# ts808_redraw.net
KiCad netlist of a schematic drawn in EAGLE
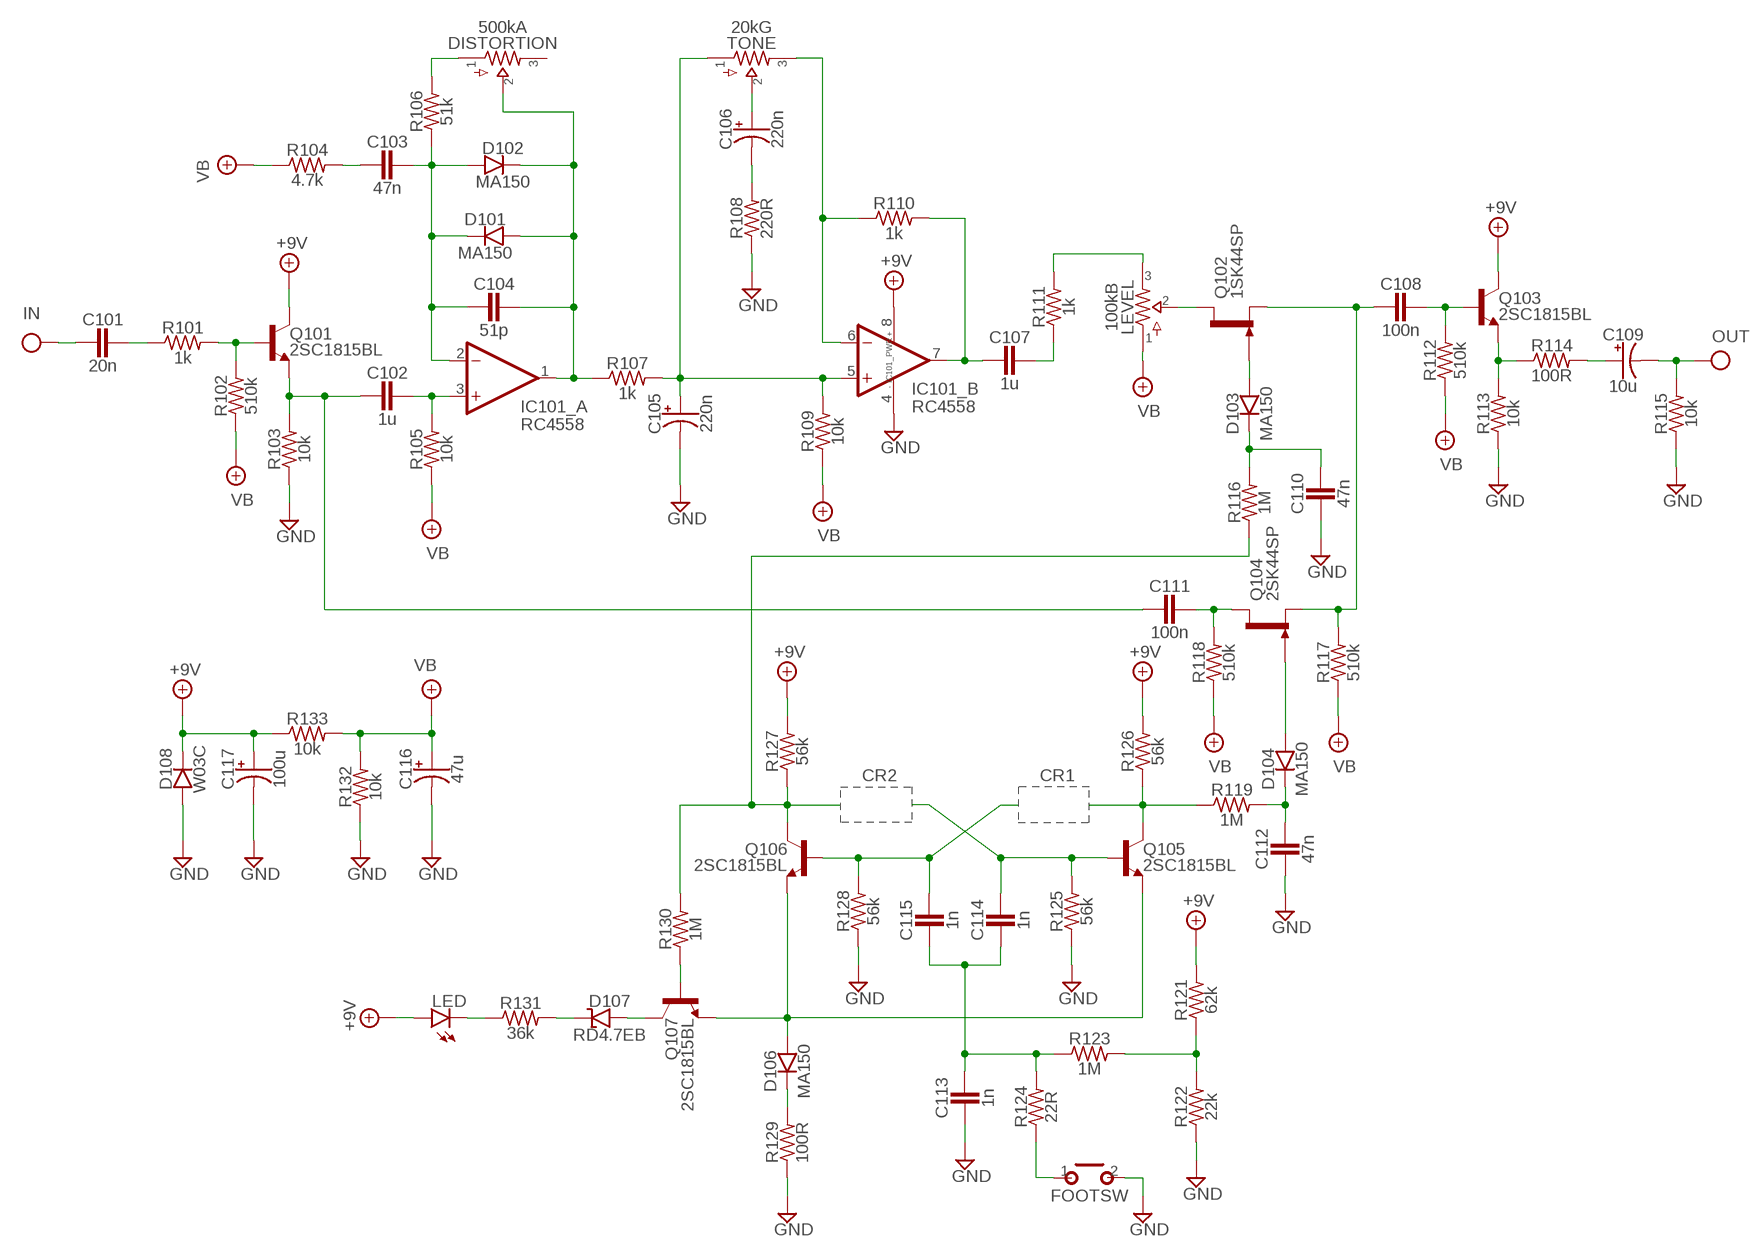
[diagram p0: schematic, sheet 1]

(export (version "E")
  (design (tool "Eeschema 10.0.6"))
  (components
    (comp (ref "C101")
      (value "20n")
      (footprint "eagle-import:BOX_SMALL")
      (libsource (lib "eagle-import") (part "CER/FILMBOX.1"))
    )
    (comp (ref "C102")
      (value "1u")
      (footprint "eagle-import:BOX_SMALL")
      (libsource (lib "eagle-import") (part "CER/FILMBOX.1"))
    )
    (comp (ref "C103")
      (value "47n")
      (footprint "eagle-import:BOX_SMALL")
      (libsource (lib "eagle-import") (part "CER/FILMBOX.1"))
    )
    (comp (ref "C104")
      (value "51p")
      (footprint "eagle-import:BOX_SMALL")
      (libsource (lib "eagle-import") (part "CER/FILMBOX.1"))
    )
    (comp (ref "C105")
      (value "220n")
      (footprint "eagle-import:050_020")
      (libsource (lib "eagle-import") (part "0500"))
    )
    (comp (ref "C106")
      (value "220n")
      (footprint "eagle-import:050_020")
      (libsource (lib "eagle-import") (part "0500"))
    )
    (comp (ref "C107")
      (value "1u")
      (footprint "eagle-import:BOX_SMALL")
      (libsource (lib "eagle-import") (part "CER/FILMBOX.1"))
    )
    (comp (ref "C108")
      (value "100n")
      (footprint "eagle-import:BOX_SMALL")
      (libsource (lib "eagle-import") (part "CER/FILMBOX.1"))
    )
    (comp (ref "C109")
      (value "10u")
      (footprint "eagle-import:050_020")
      (libsource (lib "eagle-import") (part "0500"))
    )
    (comp (ref "C110")
      (value "47n")
      (footprint "eagle-import:BOX_SMALL")
      (libsource (lib "eagle-import") (part "CER/FILMBOX.1"))
    )
    (comp (ref "C111")
      (value "100n")
      (footprint "eagle-import:BOX_SMALL")
      (libsource (lib "eagle-import") (part "CER/FILMBOX.1"))
    )
    (comp (ref "C112")
      (value "47n")
      (footprint "eagle-import:BOX_SMALL")
      (libsource (lib "eagle-import") (part "CER/FILMBOX.1"))
    )
    (comp (ref "C113")
      (value "1n")
      (footprint "eagle-import:BOX_SMALL")
      (libsource (lib "eagle-import") (part "CER/FILMBOX.1"))
    )
    (comp (ref "C114")
      (value "1n")
      (footprint "eagle-import:BOX_SMALL")
      (libsource (lib "eagle-import") (part "CER/FILMBOX.1"))
    )
    (comp (ref "C115")
      (value "1n")
      (footprint "eagle-import:BOX_SMALL")
      (libsource (lib "eagle-import") (part "CER/FILMBOX.1"))
    )
    (comp (ref "C116")
      (value "47u")
      (footprint "eagle-import:050_020")
      (libsource (lib "eagle-import") (part "0500"))
    )
    (comp (ref "C117")
      (value "100u")
      (footprint "eagle-import:050_020")
      (libsource (lib "eagle-import") (part "0500"))
    )
    (comp (ref "D101")
      (value "MA150")
      (footprint "eagle-import:DO35-2")
      (libsource (lib "eagle-import") (part "DO35.2"))
    )
    (comp (ref "D102")
      (value "MA150")
      (footprint "eagle-import:DO35-2")
      (libsource (lib "eagle-import") (part "DO35.2"))
    )
    (comp (ref "D103")
      (value "MA150")
      (footprint "eagle-import:DO35-2")
      (libsource (lib "eagle-import") (part "DO35.2"))
    )
    (comp (ref "D104")
      (value "MA150")
      (footprint "eagle-import:DO35-2")
      (libsource (lib "eagle-import") (part "DO35.2"))
    )
    (comp (ref "D106")
      (value "MA150")
      (footprint "eagle-import:DO35-2")
      (libsource (lib "eagle-import") (part "DO35.2"))
    )
    (comp (ref "D107")
      (value "RD4.7EB")
      (footprint "eagle-import:DO41-2")
      (libsource (lib "eagle-import") (part "ZENER.2"))
    )
    (comp (ref "D108")
      (value "W03C")
      (footprint "eagle-import:DO35-2")
      (libsource (lib "eagle-import") (part "DO35.2"))
    )
    (comp (ref "DISTORTION")
      (value "500kA")
      (footprint "eagle-import:16MM")
      (libsource (lib "eagle-import") (part "POTS16MM"))
    )
    (comp (ref "FOOTSW")
      (value "MOMENTARY")
      (footprint "eagle-import:SPST")
      (libsource (lib "eagle-import") (part "MOMENTARY"))
    )
    (comp (ref "IC101")
      (value "RC4558")
      (footprint "eagle-import:DIL0")
      (libsource (lib "eagle-import") (part "DUALTH"))
    )
    (comp (ref "LED")
      (value "LED")
      (footprint "eagle-import:3MM_D")
      (libsource (lib "eagle-import") (part "LED"))
    )
    (comp (ref "LEVEL")
      (value "100kB")
      (footprint "eagle-import:16MM")
      (libsource (lib "eagle-import") (part "POTS16MM"))
    )
    (comp (ref "Q101")
      (value "2SC1815BL")
      (footprint "eagle-import:TO92-")
      (libsource (lib "eagle-import") (part "2N3904"))
    )
    (comp (ref "Q102")
      (value "1SK44SP")
      (footprint "eagle-import:TO92-")
      (libsource (lib "eagle-import") (part "2N5457"))
    )
    (comp (ref "Q103")
      (value "2SC1815BL")
      (footprint "eagle-import:TO92-")
      (libsource (lib "eagle-import") (part "2N3904"))
    )
    (comp (ref "Q104")
      (value "2SK44SP")
      (footprint "eagle-import:TO92-")
      (libsource (lib "eagle-import") (part "2N5457"))
    )
    (comp (ref "Q105")
      (value "2SC1815BL")
      (footprint "eagle-import:TO92-")
      (libsource (lib "eagle-import") (part "2SC828A"))
    )
    (comp (ref "Q106")
      (value "2SC1815BL")
      (footprint "eagle-import:TO92-")
      (libsource (lib "eagle-import") (part "2SC828A"))
    )
    (comp (ref "Q107")
      (value "2SC1815BL")
      (footprint "eagle-import:TO92-")
      (libsource (lib "eagle-import") (part "2SC828A"))
    )
    (comp (ref "R101")
      (value "1k")
      (footprint "eagle-import:R0207_3")
      (libsource (lib "eagle-import") (part "R_.3B"))
    )
    (comp (ref "R102")
      (value "510k")
      (footprint "eagle-import:R0207_3")
      (libsource (lib "eagle-import") (part "R_.3B"))
    )
    (comp (ref "R103")
      (value "10k")
      (footprint "eagle-import:R0207_3")
      (libsource (lib "eagle-import") (part "R_.3B"))
    )
    (comp (ref "R104")
      (value "4.7k")
      (footprint "eagle-import:R0207_3")
      (libsource (lib "eagle-import") (part "R_.3B"))
    )
    (comp (ref "R105")
      (value "10k")
      (footprint "eagle-import:R0207_3")
      (libsource (lib "eagle-import") (part "R_.3B"))
    )
    (comp (ref "R106")
      (value "51k")
      (footprint "eagle-import:R0207_3")
      (libsource (lib "eagle-import") (part "R_.3B"))
    )
    (comp (ref "R107")
      (value "1k")
      (footprint "eagle-import:R0207_3")
      (libsource (lib "eagle-import") (part "R_.3B"))
    )
    (comp (ref "R108")
      (value "220R")
      (footprint "eagle-import:R0207_3")
      (libsource (lib "eagle-import") (part "R_.3B"))
    )
    (comp (ref "R109")
      (value "10k")
      (footprint "eagle-import:R0207_3")
      (libsource (lib "eagle-import") (part "R_.3B"))
    )
    (comp (ref "R110")
      (value "1k")
      (footprint "eagle-import:R0207_3")
      (libsource (lib "eagle-import") (part "R_.3B"))
    )
    (comp (ref "R111")
      (value "1k")
      (footprint "eagle-import:R0207_3")
      (libsource (lib "eagle-import") (part "R_.3B"))
    )
    (comp (ref "R112")
      (value "510k")
      (footprint "eagle-import:R0207_3")
      (libsource (lib "eagle-import") (part "R_.3B"))
    )
    (comp (ref "R113")
      (value "10k")
      (footprint "eagle-import:R0207_3")
      (libsource (lib "eagle-import") (part "R_.3B"))
    )
    (comp (ref "R114")
      (value "100R")
      (footprint "eagle-import:R0207_3")
      (libsource (lib "eagle-import") (part "R_.3B"))
    )
    (comp (ref "R115")
      (value "10k")
      (footprint "eagle-import:R0207_3")
      (libsource (lib "eagle-import") (part "R_.3B"))
    )
    (comp (ref "R116")
      (value "1M")
      (footprint "eagle-import:R0207_3")
      (libsource (lib "eagle-import") (part "R_.3B"))
    )
    (comp (ref "R117")
      (value "510k")
      (footprint "eagle-import:R0207_3")
      (libsource (lib "eagle-import") (part "R_.3B"))
    )
    (comp (ref "R118")
      (value "510k")
      (footprint "eagle-import:R0207_3")
      (libsource (lib "eagle-import") (part "R_.3B"))
    )
    (comp (ref "R119")
      (value "1M")
      (footprint "eagle-import:R0207_3")
      (libsource (lib "eagle-import") (part "R_.3B"))
    )
    (comp (ref "R121")
      (value "62k")
      (footprint "eagle-import:R0207_3")
      (libsource (lib "eagle-import") (part "R_.3B"))
    )
    (comp (ref "R122")
      (value "22k")
      (footprint "eagle-import:R0207_3")
      (libsource (lib "eagle-import") (part "R_.3B"))
    )
    (comp (ref "R123")
      (value "1M")
      (footprint "eagle-import:R0207_3")
      (libsource (lib "eagle-import") (part "R_.3B"))
    )
    (comp (ref "R124")
      (value "22R")
      (footprint "eagle-import:R0207_3")
      (libsource (lib "eagle-import") (part "R_.3B"))
    )
    (comp (ref "R125")
      (value "56k")
      (footprint "eagle-import:R0207_3")
      (libsource (lib "eagle-import") (part "R_.3B"))
    )
    (comp (ref "R126")
      (value "56k")
      (footprint "eagle-import:R0207_3")
      (libsource (lib "eagle-import") (part "R_.3B"))
    )
    (comp (ref "R127")
      (value "56k")
      (footprint "eagle-import:R0207_3")
      (libsource (lib "eagle-import") (part "R_.3B"))
    )
    (comp (ref "R128")
      (value "56k")
      (footprint "eagle-import:R0207_3")
      (libsource (lib "eagle-import") (part "R_.3B"))
    )
    (comp (ref "R129")
      (value "100R")
      (footprint "eagle-import:R0207_3")
      (libsource (lib "eagle-import") (part "R_.3B"))
    )
    (comp (ref "R130")
      (value "1M")
      (footprint "eagle-import:R0207_3")
      (libsource (lib "eagle-import") (part "R_.3B"))
    )
    (comp (ref "R131")
      (value "36k")
      (footprint "eagle-import:R0207_3")
      (libsource (lib "eagle-import") (part "R_.3B"))
    )
    (comp (ref "R132")
      (value "10k")
      (footprint "eagle-import:R0207_3")
      (libsource (lib "eagle-import") (part "R_.3B"))
    )
    (comp (ref "R133")
      (value "10k")
      (footprint "eagle-import:R0207_3")
      (libsource (lib "eagle-import") (part "R_.3B"))
    )
    (comp (ref "TONE")
      (value "20kG")
      (footprint "eagle-import:16MM")
      (libsource (lib "eagle-import") (part "POTS16MM"))
    )
  )
  (nets
    (net (code "1") (name "+9V") (class "Default")
      (node (ref "C117") (pin "+") (pinfunction "+_+") (pintype "passive"))
      (node (ref "D108") (pin "C") (pinfunction "C_C") (pintype "passive"))
      (node (ref "IC101") (pin "8") (pinfunction "V+_8") (pintype "power_in"))
      (node (ref "LED") (pin "ANODE") (pinfunction "A_ANODE") (pintype "passive"))
      (node (ref "Q101") (pin "1") (pinfunction "C_1") (pintype "passive"))
      (node (ref "Q103") (pin "1") (pinfunction "C_1") (pintype "passive"))
      (node (ref "R121") (pin "2") (pinfunction "2_2") (pintype "passive"))
      (node (ref "R126") (pin "2") (pinfunction "2_2") (pintype "passive"))
      (node (ref "R127") (pin "2") (pinfunction "2_2") (pintype "passive"))
      (node (ref "R133") (pin "1") (pinfunction "1_1") (pintype "passive"))
    )
    (net (code "2") (name "GND") (class "Default")
      (node (ref "C105") (pin "-") (pinfunction "-_-") (pintype "passive"))
      (node (ref "C110") (pin "2") (pinfunction "2_2") (pintype "passive"))
      (node (ref "C112") (pin "2") (pinfunction "2_2") (pintype "passive"))
      (node (ref "C113") (pin "2") (pinfunction "2_2") (pintype "passive"))
      (node (ref "C116") (pin "-") (pinfunction "-_-") (pintype "passive"))
      (node (ref "C117") (pin "-") (pinfunction "-_-") (pintype "passive"))
      (node (ref "D108") (pin "A") (pinfunction "A_A") (pintype "passive"))
      (node (ref "FOOTSW") (pin "2") (pinfunction "S_2") (pintype "passive"))
      (node (ref "IC101") (pin "4") (pinfunction "V-_4") (pintype "power_in"))
      (node (ref "R103") (pin "1") (pinfunction "1_1") (pintype "passive"))
      (node (ref "R108") (pin "1") (pinfunction "1_1") (pintype "passive"))
      (node (ref "R113") (pin "1") (pinfunction "1_1") (pintype "passive"))
      (node (ref "R115") (pin "1") (pinfunction "1_1") (pintype "passive"))
      (node (ref "R122") (pin "1") (pinfunction "1_1") (pintype "passive"))
      (node (ref "R125") (pin "1") (pinfunction "1_1") (pintype "passive"))
      (node (ref "R128") (pin "1") (pinfunction "1_1") (pintype "passive"))
      (node (ref "R129") (pin "1") (pinfunction "1_1") (pintype "passive"))
      (node (ref "R132") (pin "1") (pinfunction "1_1") (pintype "passive"))
    )
    (net (code "3") (name "IN") (class "Default")
      (node (ref "C101") (pin "2") (pinfunction "2_2") (pintype "passive"))
    )
    (net (code "4") (name "Net-(C101-Pad1)") (class "Default")
      (node (ref "C101") (pin "1") (pinfunction "1_1") (pintype "passive"))
      (node (ref "R101") (pin "1") (pinfunction "1_1") (pintype "passive"))
    )
    (net (code "5") (name "Net-(C103-Pad2)") (class "Default")
      (node (ref "C103") (pin "2") (pinfunction "2_2") (pintype "passive"))
      (node (ref "R104") (pin "2") (pinfunction "2_2") (pintype "passive"))
    )
    (net (code "6") (name "Net-(C106-Pad+)") (class "Default")
      (node (ref "C106") (pin "+") (pinfunction "+_+") (pintype "passive"))
      (node (ref "TONE") (pin "2") (pinfunction "2_2") (pintype "passive"))
    )
    (net (code "7") (name "Net-(C106-Pad-)") (class "Default")
      (node (ref "C106") (pin "-") (pinfunction "-_-") (pintype "passive"))
      (node (ref "R108") (pin "2") (pinfunction "2_2") (pintype "passive"))
    )
    (net (code "8") (name "Net-(C107-Pad1)") (class "Default")
      (node (ref "C107") (pin "1") (pinfunction "1_1") (pintype "passive"))
      (node (ref "R111") (pin "1") (pinfunction "1_1") (pintype "passive"))
    )
    (net (code "9") (name "Net-(C109-Pad+)") (class "Default")
      (node (ref "C109") (pin "+") (pinfunction "+_+") (pintype "passive"))
      (node (ref "R114") (pin "2") (pinfunction "2_2") (pintype "passive"))
    )
    (net (code "10") (name "Net-(C110-Pad1)") (class "Default")
      (node (ref "C110") (pin "1") (pinfunction "1_1") (pintype "passive"))
      (node (ref "D103") (pin "C") (pinfunction "C_C") (pintype "passive"))
      (node (ref "R116") (pin "2") (pinfunction "2_2") (pintype "passive"))
    )
    (net (code "11") (name "Net-(C112-Pad1)") (class "Default")
      (node (ref "C112") (pin "1") (pinfunction "1_1") (pintype "passive"))
      (node (ref "D104") (pin "C") (pinfunction "C_C") (pintype "passive"))
      (node (ref "R119") (pin "2") (pinfunction "2_2") (pintype "passive"))
    )
    (net (code "12") (name "Net-(C113-Pad1)") (class "Default")
      (node (ref "C113") (pin "1") (pinfunction "1_1") (pintype "passive"))
      (node (ref "C114") (pin "2") (pinfunction "2_2") (pintype "passive"))
      (node (ref "C115") (pin "2") (pinfunction "2_2") (pintype "passive"))
      (node (ref "R123") (pin "1") (pinfunction "1_1") (pintype "passive"))
      (node (ref "R124") (pin "2") (pinfunction "2_2") (pintype "passive"))
    )
    (net (code "13") (name "Net-(D106-PadC)") (class "Default")
      (node (ref "D106") (pin "C") (pinfunction "C_C") (pintype "passive"))
      (node (ref "R129") (pin "2") (pinfunction "2_2") (pintype "passive"))
    )
    (net (code "14") (name "Net-(D107-PadC)") (class "Default")
      (node (ref "D107") (pin "C") (pinfunction "C_C") (pintype "passive"))
      (node (ref "R131") (pin "2") (pinfunction "2_2") (pintype "passive"))
    )
    (net (code "15") (name "Net-(DISTORTION-Pad1)") (class "Default")
      (node (ref "DISTORTION") (pin "1") (pinfunction "1_1") (pintype "passive"))
      (node (ref "R106") (pin "2") (pinfunction "2_2") (pintype "passive"))
    )
    (net (code "16") (name "Net-(FOOTSW-P)") (class "Default")
      (node (ref "FOOTSW") (pin "1") (pinfunction "P_1") (pintype "passive"))
      (node (ref "R124") (pin "1") (pinfunction "1_1") (pintype "passive"))
    )
    (net (code "17") (name "Net-(IC101A-+IN)") (class "Default")
      (node (ref "C102") (pin "1") (pinfunction "1_1") (pintype "passive"))
      (node (ref "IC101") (pin "3") (pinfunction "+IN_3") (pintype "input"))
      (node (ref "R105") (pin "2") (pinfunction "2_2") (pintype "passive"))
    )
    (net (code "18") (name "Net-(IC101A--IN)") (class "Default")
      (node (ref "C103") (pin "1") (pinfunction "1_1") (pintype "passive"))
      (node (ref "C104") (pin "2") (pinfunction "2_2") (pintype "passive"))
      (node (ref "D101") (pin "C") (pinfunction "C_C") (pintype "passive"))
      (node (ref "D102") (pin "A") (pinfunction "A_A") (pintype "passive"))
      (node (ref "IC101") (pin "2") (pinfunction "-IN_2") (pintype "input"))
      (node (ref "R106") (pin "1") (pinfunction "1_1") (pintype "passive"))
    )
    (net (code "19") (name "Net-(IC101A-OUT)") (class "Default")
      (node (ref "C104") (pin "1") (pinfunction "1_1") (pintype "passive"))
      (node (ref "D101") (pin "A") (pinfunction "A_A") (pintype "passive"))
      (node (ref "D102") (pin "C") (pinfunction "C_C") (pintype "passive"))
      (node (ref "DISTORTION") (pin "2") (pinfunction "2_2") (pintype "passive"))
      (node (ref "IC101") (pin "1") (pinfunction "OUT_1") (pintype "output"))
      (node (ref "R107") (pin "1") (pinfunction "1_1") (pintype "passive"))
    )
    (net (code "20") (name "Net-(IC101B-+IN)") (class "Default")
      (node (ref "C105") (pin "+") (pinfunction "+_+") (pintype "passive"))
      (node (ref "IC101") (pin "5") (pinfunction "+IN_5") (pintype "input"))
      (node (ref "R107") (pin "2") (pinfunction "2_2") (pintype "passive"))
      (node (ref "R109") (pin "2") (pinfunction "2_2") (pintype "passive"))
      (node (ref "TONE") (pin "1") (pinfunction "1_1") (pintype "passive"))
    )
    (net (code "21") (name "Net-(IC101B--IN)") (class "Default")
      (node (ref "IC101") (pin "6") (pinfunction "-IN_6") (pintype "input"))
      (node (ref "R110") (pin "1") (pinfunction "1_1") (pintype "passive"))
      (node (ref "TONE") (pin "3") (pinfunction "3_3") (pintype "passive"))
    )
    (net (code "22") (name "Net-(IC101B-OUT)") (class "Default")
      (node (ref "C107") (pin "2") (pinfunction "2_2") (pintype "passive"))
      (node (ref "IC101") (pin "7") (pinfunction "OUT_7") (pintype "output"))
      (node (ref "R110") (pin "2") (pinfunction "2_2") (pintype "passive"))
    )
    (net (code "23") (name "Net-(LED-C)") (class "Default")
      (node (ref "LED") (pin "P$1") (pinfunction "C_P$1") (pintype "passive"))
      (node (ref "R131") (pin "1") (pinfunction "1_1") (pintype "passive"))
    )
    (net (code "24") (name "Net-(LEVEL-Pad3)") (class "Default")
      (node (ref "LEVEL") (pin "3") (pinfunction "3_3") (pintype "passive"))
      (node (ref "R111") (pin "2") (pinfunction "2_2") (pintype "passive"))
    )
    (net (code "25") (name "Net-(Q101-B)") (class "Default")
      (node (ref "Q101") (pin "2") (pinfunction "B_2") (pintype "passive"))
      (node (ref "R101") (pin "2") (pinfunction "2_2") (pintype "passive"))
      (node (ref "R102") (pin "2") (pinfunction "2_2") (pintype "passive"))
    )
    (net (code "26") (name "Net-(Q101-E)") (class "Default")
      (node (ref "C102") (pin "2") (pinfunction "2_2") (pintype "passive"))
      (node (ref "C111") (pin "2") (pinfunction "2_2") (pintype "passive"))
      (node (ref "Q101") (pin "3") (pinfunction "E_3") (pintype "passive"))
      (node (ref "R103") (pin "2") (pinfunction "2_2") (pintype "passive"))
    )
    (net (code "27") (name "Net-(Q102-D)") (class "Default")
      (node (ref "LEVEL") (pin "2") (pinfunction "2_2") (pintype "passive"))
      (node (ref "Q102") (pin "3") (pinfunction "D_3") (pintype "passive"))
    )
    (net (code "28") (name "Net-(Q102-G)") (class "Default")
      (node (ref "D103") (pin "A") (pinfunction "A_A") (pintype "passive"))
      (node (ref "Q102") (pin "1") (pinfunction "G_1") (pintype "passive"))
    )
    (net (code "29") (name "Net-(Q102-S)") (class "Default")
      (node (ref "C108") (pin "2") (pinfunction "2_2") (pintype "passive"))
      (node (ref "Q102") (pin "2") (pinfunction "S_2") (pintype "passive"))
      (node (ref "Q104") (pin "2") (pinfunction "S_2") (pintype "passive"))
      (node (ref "R117") (pin "2") (pinfunction "2_2") (pintype "passive"))
    )
    (net (code "30") (name "Net-(Q103-B)") (class "Default")
      (node (ref "C108") (pin "1") (pinfunction "1_1") (pintype "passive"))
      (node (ref "Q103") (pin "2") (pinfunction "B_2") (pintype "passive"))
      (node (ref "R112") (pin "2") (pinfunction "2_2") (pintype "passive"))
    )
    (net (code "31") (name "Net-(Q103-E)") (class "Default")
      (node (ref "Q103") (pin "3") (pinfunction "E_3") (pintype "passive"))
      (node (ref "R113") (pin "2") (pinfunction "2_2") (pintype "passive"))
      (node (ref "R114") (pin "1") (pinfunction "1_1") (pintype "passive"))
    )
    (net (code "32") (name "Net-(Q104-D)") (class "Default")
      (node (ref "C111") (pin "1") (pinfunction "1_1") (pintype "passive"))
      (node (ref "Q104") (pin "3") (pinfunction "D_3") (pintype "passive"))
      (node (ref "R118") (pin "2") (pinfunction "2_2") (pintype "passive"))
    )
    (net (code "33") (name "Net-(Q104-G)") (class "Default")
      (node (ref "D104") (pin "A") (pinfunction "A_A") (pintype "passive"))
      (node (ref "Q104") (pin "1") (pinfunction "G_1") (pintype "passive"))
    )
    (net (code "34") (name "Net-(Q105-B)") (class "Default")
      (node (ref "C114") (pin "1") (pinfunction "1_1") (pintype "passive"))
      (node (ref "Q105") (pin "1") (pinfunction "B_1") (pintype "passive"))
      (node (ref "R125") (pin "2") (pinfunction "2_2") (pintype "passive"))
    )
    (net (code "35") (name "Net-(Q105-C)") (class "Default")
      (node (ref "Q105") (pin "2") (pinfunction "C_2") (pintype "passive"))
      (node (ref "R119") (pin "1") (pinfunction "1_1") (pintype "passive"))
      (node (ref "R126") (pin "1") (pinfunction "1_1") (pintype "passive"))
    )
    (net (code "36") (name "Net-(Q105-E)") (class "Default")
      (node (ref "D106") (pin "A") (pinfunction "A_A") (pintype "passive"))
      (node (ref "Q105") (pin "3") (pinfunction "E_3") (pintype "passive"))
      (node (ref "Q106") (pin "3") (pinfunction "E_3") (pintype "passive"))
      (node (ref "Q107") (pin "3") (pinfunction "E_3") (pintype "passive"))
    )
    (net (code "37") (name "Net-(Q106-B)") (class "Default")
      (node (ref "C115") (pin "1") (pinfunction "1_1") (pintype "passive"))
      (node (ref "Q106") (pin "1") (pinfunction "B_1") (pintype "passive"))
      (node (ref "R128") (pin "2") (pinfunction "2_2") (pintype "passive"))
    )
    (net (code "38") (name "Net-(Q106-C)") (class "Default")
      (node (ref "Q106") (pin "2") (pinfunction "C_2") (pintype "passive"))
      (node (ref "R116") (pin "1") (pinfunction "1_1") (pintype "passive"))
      (node (ref "R127") (pin "1") (pinfunction "1_1") (pintype "passive"))
      (node (ref "R130") (pin "2") (pinfunction "2_2") (pintype "passive"))
    )
    (net (code "39") (name "Net-(Q107-B)") (class "Default")
      (node (ref "Q107") (pin "1") (pinfunction "B_1") (pintype "passive"))
      (node (ref "R130") (pin "1") (pinfunction "1_1") (pintype "passive"))
    )
    (net (code "40") (name "Net-(Q107-C)") (class "Default")
      (node (ref "D107") (pin "A") (pinfunction "A_A") (pintype "passive"))
      (node (ref "Q107") (pin "2") (pinfunction "C_2") (pintype "passive"))
    )
    (net (code "41") (name "Net-(R121-Pad1)") (class "Default")
      (node (ref "R121") (pin "1") (pinfunction "1_1") (pintype "passive"))
      (node (ref "R122") (pin "2") (pinfunction "2_2") (pintype "passive"))
      (node (ref "R123") (pin "2") (pinfunction "2_2") (pintype "passive"))
    )
    (net (code "42") (name "OUT") (class "Default")
      (node (ref "C109") (pin "-") (pinfunction "-_-") (pintype "passive"))
      (node (ref "R115") (pin "2") (pinfunction "2_2") (pintype "passive"))
    )
    (net (code "43") (name "VB") (class "Default")
      (node (ref "C116") (pin "+") (pinfunction "+_+") (pintype "passive"))
      (node (ref "LEVEL") (pin "1") (pinfunction "1_1") (pintype "passive"))
      (node (ref "R102") (pin "1") (pinfunction "1_1") (pintype "passive"))
      (node (ref "R104") (pin "1") (pinfunction "1_1") (pintype "passive"))
      (node (ref "R105") (pin "1") (pinfunction "1_1") (pintype "passive"))
      (node (ref "R109") (pin "1") (pinfunction "1_1") (pintype "passive"))
      (node (ref "R112") (pin "1") (pinfunction "1_1") (pintype "passive"))
      (node (ref "R117") (pin "1") (pinfunction "1_1") (pintype "passive"))
      (node (ref "R118") (pin "1") (pinfunction "1_1") (pintype "passive"))
      (node (ref "R132") (pin "2") (pinfunction "2_2") (pintype "passive"))
      (node (ref "R133") (pin "2") (pinfunction "2_2") (pintype "passive"))
    )
    (net (code "44") (name "unconnected-(DISTORTION-Pad3)") (class "Default")
      (node (ref "DISTORTION") (pin "3") (pinfunction "3_3") (pintype "passive"))
    )
  )
)
